# Arduino.net
KiCad netlist of a schematic drawn in EAGLE
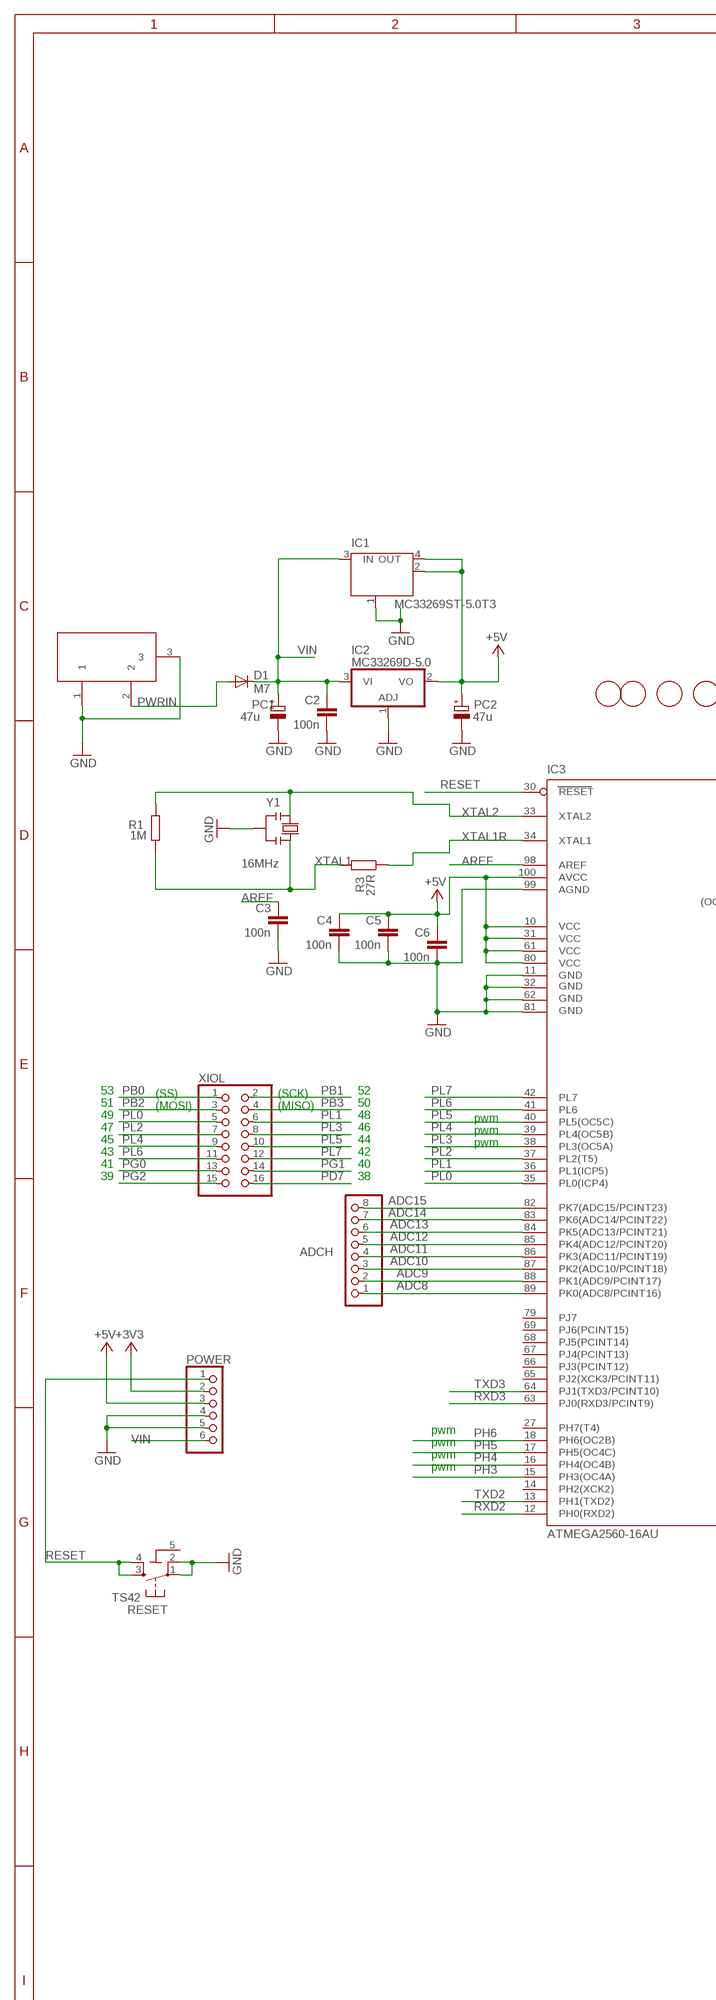
[diagram p0: schematic, sheet 1, part 1 of 2]
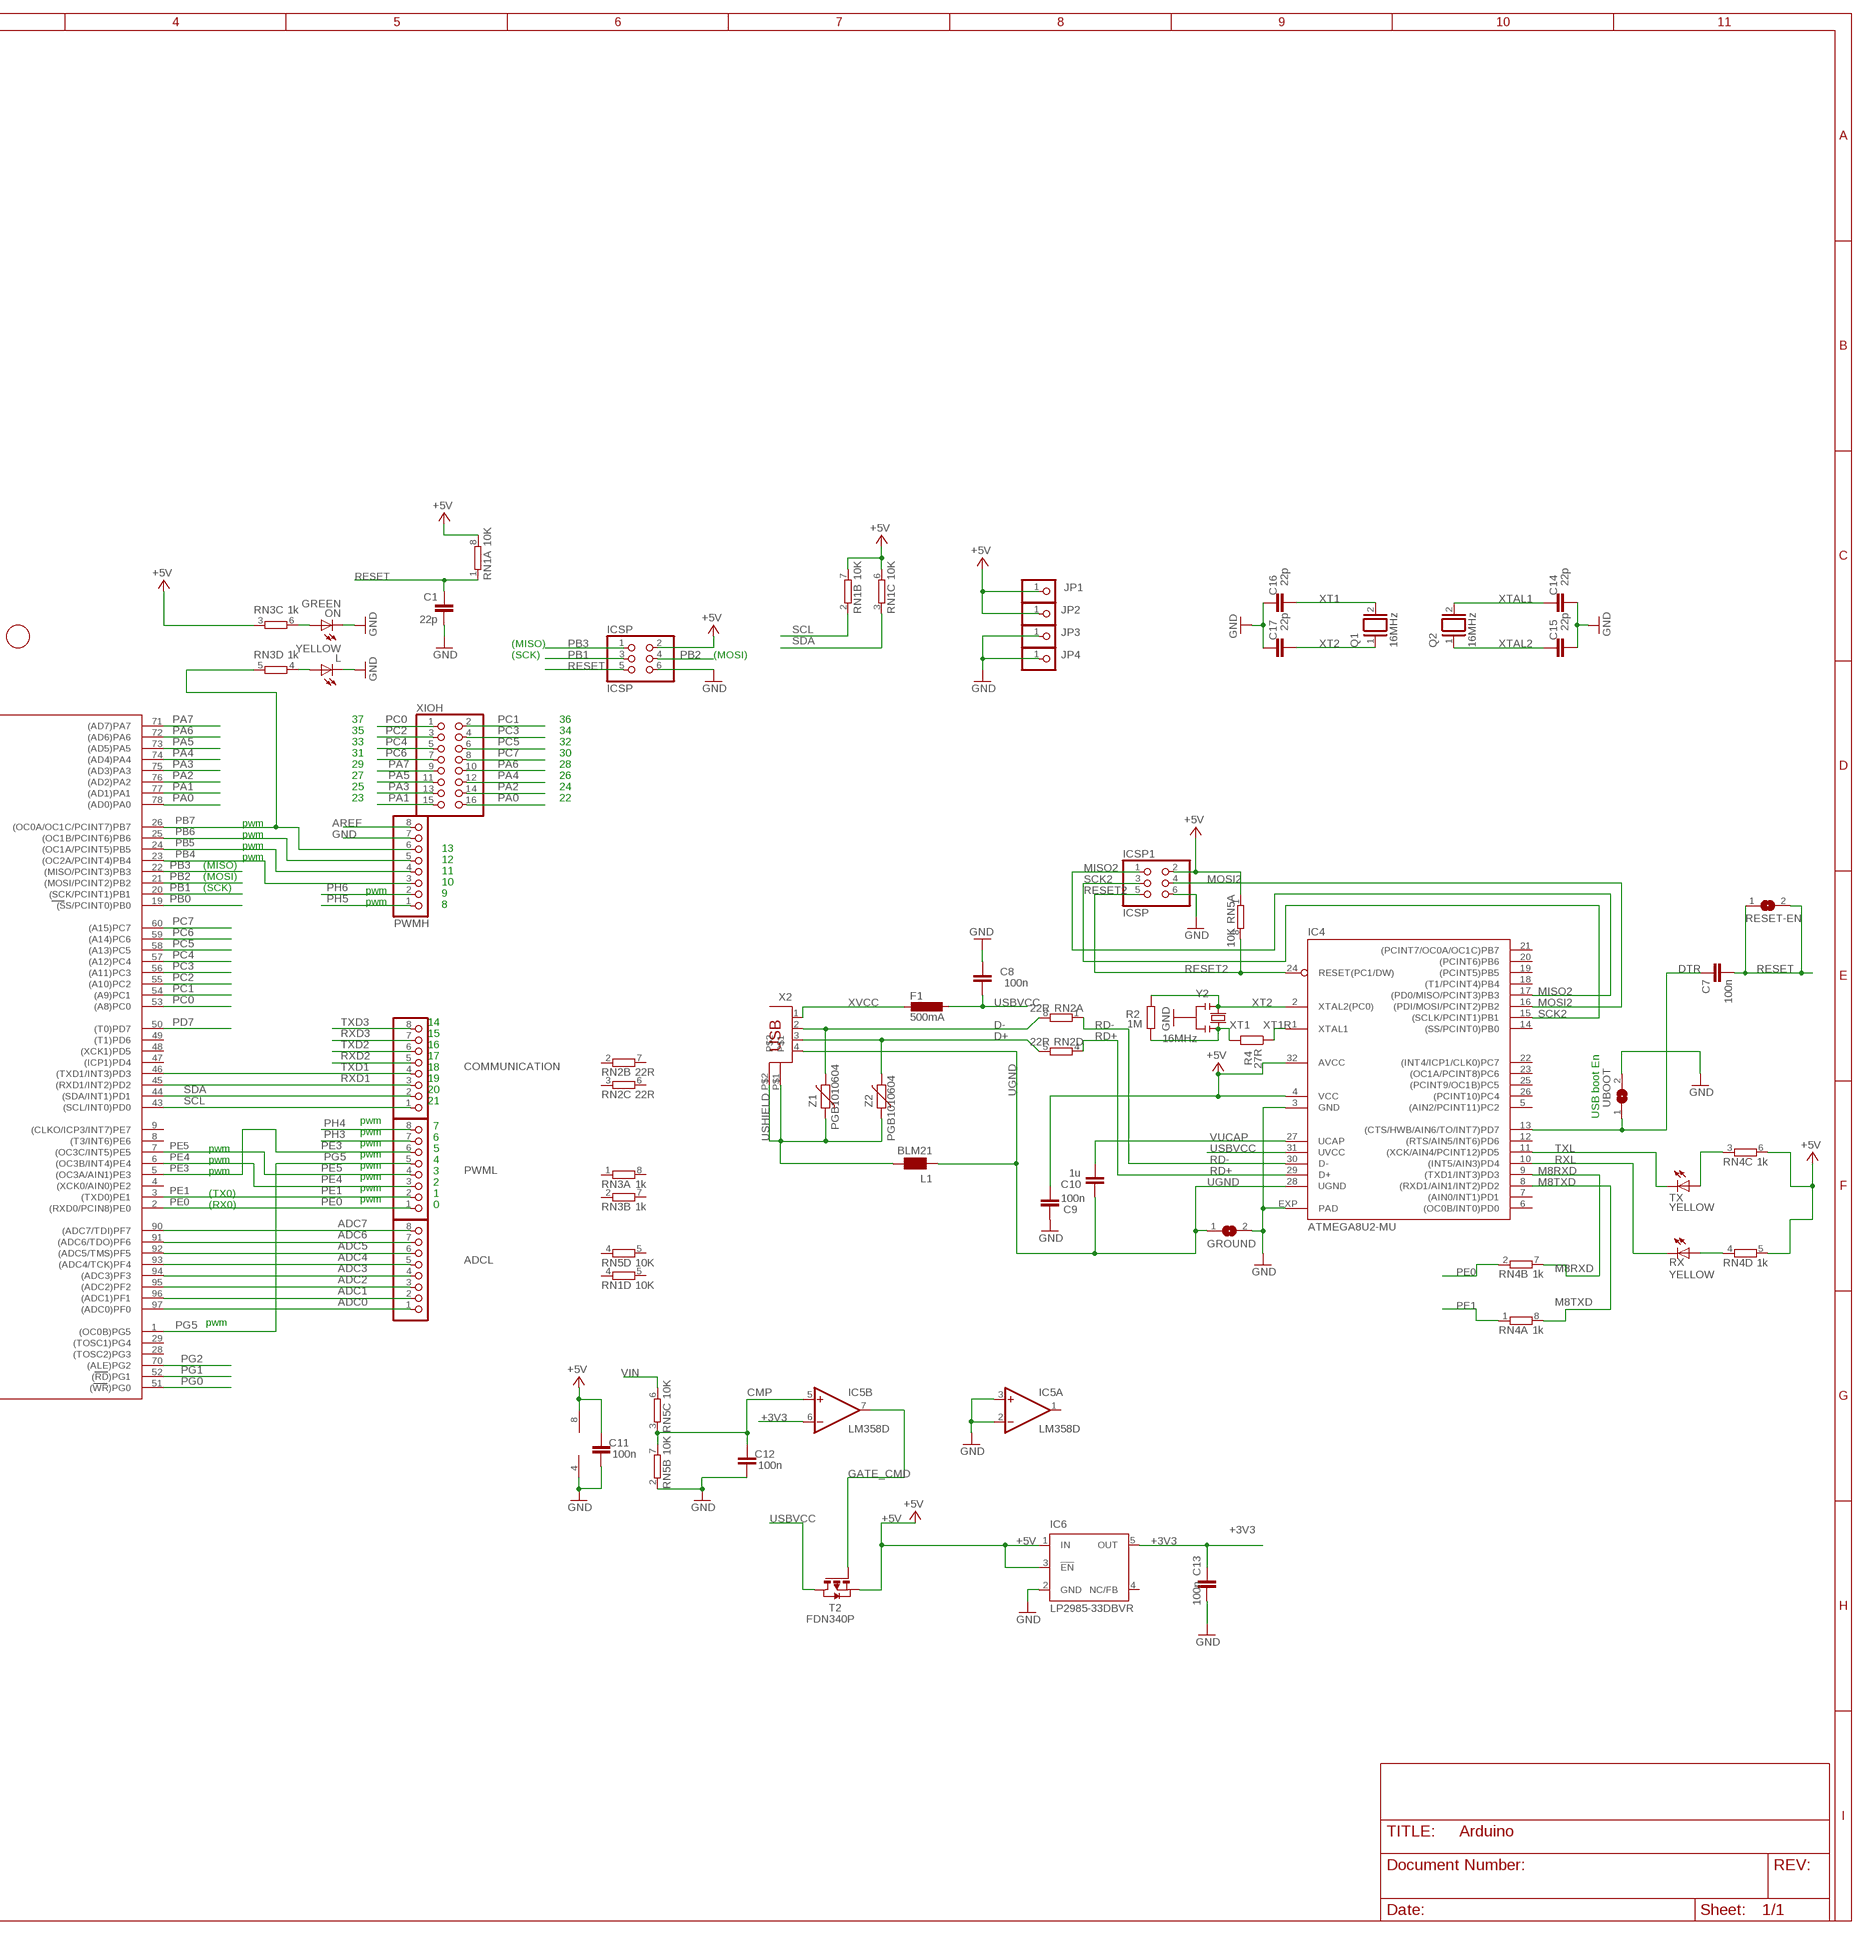
[diagram p1: schematic, sheet 1, part 2 of 2]

(export (version "E")
  (design (tool "Eeschema 10.0.6"))
  (components
    (comp (ref "ADCH")
      (value "PINHD-1X8")
      (footprint "eagle-import:1X08")
      (libsource (lib "eagle-import") (part "PINHD-1X8"))
    )
    (comp (ref "ADCL")
      (value "PINHD-1X8")
      (footprint "eagle-import:1X08")
      (libsource (lib "eagle-import") (part "PINHD-1X8"))
    )
    (comp (ref "C1")
      (value "22p")
      (footprint "eagle-import:C0603-ROUND")
      (libsource (lib "eagle-import") (part "C-EU0603-RND"))
    )
    (comp (ref "C2")
      (value "100n")
      (footprint "eagle-import:C0603-ROUND")
      (libsource (lib "eagle-import") (part "C-EU0603-RND"))
    )
    (comp (ref "C3")
      (value "100n")
      (footprint "eagle-import:C0603-ROUND")
      (libsource (lib "eagle-import") (part "C-EU0603-RND"))
    )
    (comp (ref "C4")
      (value "100n")
      (footprint "eagle-import:C0603-ROUND")
      (libsource (lib "eagle-import") (part "C-EU0603-RND"))
    )
    (comp (ref "C5")
      (value "100n")
      (footprint "eagle-import:C0603-ROUND")
      (libsource (lib "eagle-import") (part "C-EU0603-RND"))
    )
    (comp (ref "C6")
      (value "100n")
      (footprint "eagle-import:C0603-ROUND")
      (libsource (lib "eagle-import") (part "C-EU0603-RND"))
    )
    (comp (ref "C7")
      (value "100n")
      (footprint "eagle-import:C0603-ROUND")
      (libsource (lib "eagle-import") (part "C-EU0603-RND"))
    )
    (comp (ref "C8")
      (value "100n")
      (footprint "eagle-import:C0603")
      (libsource (lib "eagle-import") (part "rcl_C-EUC0603"))
    )
    (comp (ref "C9")
      (value "100n")
      (footprint "eagle-import:C0603-ROUND")
      (libsource (lib "eagle-import") (part "C-EU0603-RND"))
    )
    (comp (ref "C10")
      (value "1u")
      (footprint "eagle-import:C0603-ROUND")
      (libsource (lib "eagle-import") (part "C-EU0603-RND"))
    )
    (comp (ref "C11")
      (value "100n")
      (footprint "eagle-import:C0603")
      (libsource (lib "eagle-import") (part "rcl_C-EUC0603"))
    )
    (comp (ref "C12")
      (value "100n")
      (footprint "eagle-import:C0603-ROUND")
      (libsource (lib "eagle-import") (part "C-EU0603-RND"))
    )
    (comp (ref "C13")
      (value "100n")
      (footprint "eagle-import:C0603-ROUND")
      (libsource (lib "eagle-import") (part "C-EU0603-RND"))
    )
    (comp (ref "C14")
      (value "22p")
      (footprint "eagle-import:C0603-ROUND")
      (libsource (lib "eagle-import") (part "C-EU0603-RND"))
    )
    (comp (ref "C15")
      (value "22p")
      (footprint "eagle-import:C0603-ROUND")
      (libsource (lib "eagle-import") (part "C-EU0603-RND"))
    )
    (comp (ref "C16")
      (value "22p")
      (footprint "eagle-import:C0603-ROUND")
      (libsource (lib "eagle-import") (part "C-EU0603-RND"))
    )
    (comp (ref "C17")
      (value "22p")
      (footprint "eagle-import:C0603-ROUND")
      (libsource (lib "eagle-import") (part "C-EU0603-RND"))
    )
    (comp (ref "COMMUNICATION")
      (value "PINHD-1X8")
      (footprint "eagle-import:1X08")
      (libsource (lib "eagle-import") (part "PINHD-1X8"))
    )
    (comp (ref "D1")
      (value "M7")
      (footprint "eagle-import:SMB")
      (libsource (lib "eagle-import") (part "DIODE-SMB"))
    )
    (comp (ref "F1")
      (value "500mA")
      (footprint "eagle-import:L1812")
      (libsource (lib "eagle-import") (part "L-EUL1812"))
    )
    (comp (ref "GROUND")
      (value "SJ")
      (footprint "eagle-import:SJ")
      (libsource (lib "eagle-import") (part "SJ"))
    )
    (comp (ref "IC1")
      (value "MC33269ST-5.0T3")
      (footprint "eagle-import:SOT223")
      (libsource (lib "eagle-import") (part "MC33269ST-3.3T3"))
    )
    (comp (ref "IC2")
      (value "MC33269D-5.0")
      (footprint "eagle-import:DPACK")
      (libsource (lib "eagle-import") (part "MC33269?D-5.0"))
    )
    (comp (ref "IC3")
      (value "ATMEGA2560-16AU")
      (footprint "eagle-import:TQFP100")
      (libsource (lib "eagle-import") (part "ATMEGAAU1280-16"))
    )
    (comp (ref "IC4")
      (value "ATMEGA8U2-MU")
      (footprint "eagle-import:QFN32")
      (libsource (lib "eagle-import") (part "ATMEGA8U2-MU"))
    )
    (comp (ref "IC5")
      (value "LM358D")
      (footprint "eagle-import:SO08")
      (libsource (lib "eagle-import") (part "LM358D"))
    )
    (comp (ref "IC6")
      (value "LP2985-33DBVR")
      (footprint "eagle-import:SOT23-DBV")
      (libsource (lib "eagle-import") (part "TPS77033"))
    )
    (comp (ref "ICSP")
      (value "ICSP")
      (footprint "eagle-import:2X03")
      (libsource (lib "eagle-import") (part "PINHD-2X3"))
    )
    (comp (ref "ICSP1")
      (value "ICSP")
      (footprint "eagle-import:2X03")
      (libsource (lib "eagle-import") (part "PINHD-2X3"))
    )
    (comp (ref "JP1")
      (value "PINHD-1X1")
      (footprint "eagle-import:1X01")
      (libsource (lib "eagle-import") (part "PINHD-1X1"))
    )
    (comp (ref "JP2")
      (value "PINHD-1X1")
      (footprint "eagle-import:1X01")
      (libsource (lib "eagle-import") (part "PINHD-1X1"))
    )
    (comp (ref "JP3")
      (value "PINHD-1X1")
      (footprint "eagle-import:1X01")
      (libsource (lib "eagle-import") (part "PINHD-1X1"))
    )
    (comp (ref "JP4")
      (value "PINHD-1X1")
      (footprint "eagle-import:1X01")
      (libsource (lib "eagle-import") (part "PINHD-1X1"))
    )
    (comp (ref "L")
      (value "YELLOW")
      (footprint "eagle-import:CHIP-LED0805")
      (libsource (lib "eagle-import") (part "LEDCHIP-LED0805"))
    )
    (comp (ref "L1")
      (value "BLM21")
      (footprint "eagle-import:0805")
      (libsource (lib "eagle-import") (part "WE-CBF_0805"))
    )
    (comp (ref "ON")
      (value "GREEN")
      (footprint "eagle-import:CHIP-LED0805")
      (libsource (lib "eagle-import") (part "LEDCHIP-LED0805"))
    )
    (comp (ref "PC1")
      (value "47u")
      (footprint "eagle-import:PANASONIC_D")
      (libsource (lib "eagle-import") (part "CPOL-EUD"))
    )
    (comp (ref "PC2")
      (value "47u")
      (footprint "eagle-import:PANASONIC_D")
      (libsource (lib "eagle-import") (part "CPOL-EUD"))
    )
    (comp (ref "POWER")
      (value "PINHD-1X6")
      (footprint "eagle-import:1X06")
      (libsource (lib "eagle-import") (part "PINHD-1X6"))
    )
    (comp (ref "PWMH")
      (value "PINHD-1X8")
      (footprint "eagle-import:1X08")
      (libsource (lib "eagle-import") (part "PINHD-1X8"))
    )
    (comp (ref "PWML")
      (value "PINHD-1X8")
      (footprint "eagle-import:1X08")
      (libsource (lib "eagle-import") (part "PINHD-1X8"))
    )
    (comp (ref "Q1")
      (value "16MHz")
      (footprint "eagle-import:QS")
      (libsource (lib "eagle-import") (part "XTAL/S"))
    )
    (comp (ref "Q2")
      (value "16MHz")
      (footprint "eagle-import:QS")
      (libsource (lib "eagle-import") (part "XTAL/S"))
    )
    (comp (ref "R1")
      (value "1M")
      (footprint "eagle-import:R0603-ROUND")
      (libsource (lib "eagle-import") (part "R-EU_R0603"))
    )
    (comp (ref "R2")
      (value "1M")
      (footprint "eagle-import:R0603-ROUND")
      (libsource (lib "eagle-import") (part "R-EU_R0603"))
    )
    (comp (ref "R3")
      (value "27R")
      (footprint "eagle-import:R0603-ROUND")
      (libsource (lib "eagle-import") (part "R-EU_R0603"))
    )
    (comp (ref "R4")
      (value "27R")
      (footprint "eagle-import:R0603-ROUND")
      (libsource (lib "eagle-import") (part "R-EU_R0603"))
    )
    (comp (ref "RESET")
      (value "TS42")
      (footprint "eagle-import:TS42")
      (libsource (lib "eagle-import") (part "TS42"))
    )
    (comp (ref "RESET-EN")
      (value "SJ")
      (footprint "eagle-import:SJ")
      (libsource (lib "eagle-import") (part "SJ"))
    )
    (comp (ref "RN1")
      (value "10K")
      (footprint "eagle-import:CAT16")
      (libsource (lib "eagle-import") (part "4R-NCAT16"))
    )
    (comp (ref "RN2")
      (value "22R")
      (footprint "eagle-import:CAY16")
      (libsource (lib "eagle-import") (part "4R-NCAY16"))
    )
    (comp (ref "RN3")
      (value "1k")
      (footprint "eagle-import:CAY16")
      (libsource (lib "eagle-import") (part "4R-NCAY16"))
    )
    (comp (ref "RN4")
      (value "1k")
      (footprint "eagle-import:CAY16")
      (libsource (lib "eagle-import") (part "4R-NCAY16"))
    )
    (comp (ref "RN5")
      (value "10K")
      (footprint "eagle-import:CAT16")
      (libsource (lib "eagle-import") (part "4R-NCAT16"))
    )
    (comp (ref "RX")
      (value "YELLOW")
      (footprint "eagle-import:CHIP-LED0805")
      (libsource (lib "eagle-import") (part "LEDCHIP-LED0805"))
    )
    (comp (ref "T2")
      (value "FDN340P")
      (footprint "eagle-import:SOT-23")
      (libsource (lib "eagle-import") (part "PMOSSOT23"))
    )
    (comp (ref "TX")
      (value "YELLOW")
      (footprint "eagle-import:CHIP-LED0805")
      (libsource (lib "eagle-import") (part "LEDCHIP-LED0805"))
    )
    (comp (ref "U$2")
      (value "FIDUCIALMOUNT")
      (footprint "eagle-import:FIDUCIA-MOUNT")
      (libsource (lib "eagle-import") (part "FIDUCIALMOUNT"))
    )
    (comp (ref "U$3")
      (value "FIDUCIALMOUNT")
      (footprint "eagle-import:FIDUCIA-MOUNT")
      (libsource (lib "eagle-import") (part "FIDUCIALMOUNT"))
    )
    (comp (ref "U$4")
      (value "FIDUCIALMOUNT")
      (footprint "eagle-import:FIDUCIA-MOUNT")
      (libsource (lib "eagle-import") (part "FIDUCIALMOUNT"))
    )
    (comp (ref "U$5")
      (value "FIDUCIALMOUNT")
      (footprint "eagle-import:FIDUCIA-MOUNT")
      (libsource (lib "eagle-import") (part "FIDUCIALMOUNT"))
    )
    (comp (ref "UBOOT")
      (value "SJ")
      (footprint "eagle-import:SJ")
      (libsource (lib "eagle-import") (part "SJ"))
    )
    (comp (ref "X1")
      (value "DC21MMX")
      (footprint "eagle-import:DC-21MM")
      (libsource (lib "eagle-import") (part "DC21MMX"))
    )
    (comp (ref "X2")
      (value "PN61729")
      (footprint "eagle-import:PN61729")
      (libsource (lib "eagle-import") (part "PN61729"))
    )
    (comp (ref "XIOH")
      (value "PINHD-2X8")
      (footprint "eagle-import:2X08")
      (libsource (lib "eagle-import") (part "PINHD-2X8"))
    )
    (comp (ref "XIOL")
      (value "PINHD-2X8")
      (footprint "eagle-import:2X08")
      (libsource (lib "eagle-import") (part "PINHD-2X8"))
    )
    (comp (ref "Y1")
      (value "16MHz")
      (footprint "eagle-import:RESONATOR")
      (libsource (lib "eagle-import") (part "RESONATORMU"))
    )
    (comp (ref "Y2")
      (value "16MHz")
      (footprint "eagle-import:RESONATOR")
      (libsource (lib "eagle-import") (part "RESONATORMU"))
    )
    (comp (ref "Z1")
      (value "PGB1010604")
      (footprint "eagle-import:CT_CN0603")
      (libsource (lib "eagle-import") (part "VARISTORCN0603"))
    )
    (comp (ref "Z2")
      (value "PGB1010604")
      (footprint "eagle-import:CT_CN0603")
      (libsource (lib "eagle-import") (part "VARISTORCN0603"))
    )
  )
  (nets
    (net (code "1") (name "+3V3") (class "Default")
      (node (ref "C13") (pin "2") (pinfunction "2_2") (pintype "passive"))
      (node (ref "IC5") (pin "6") (pinfunction "-IN_6") (pintype "input"))
      (node (ref "IC6") (pin "5") (pinfunction "OUT_5") (pintype "passive"))
      (node (ref "POWER") (pin "2") (pinfunction "2_2") (pintype "passive"))
    )
    (net (code "2") (name "+5V") (class "Default")
      (node (ref "C11") (pin "2") (pinfunction "2_2") (pintype "passive"))
      (node (ref "C4") (pin "1") (pinfunction "1_1") (pintype "passive"))
      (node (ref "C5") (pin "1") (pinfunction "1_1") (pintype "passive"))
      (node (ref "C6") (pin "1") (pinfunction "1_1") (pintype "passive"))
      (node (ref "C9") (pin "1") (pinfunction "1_1") (pintype "passive"))
      (node (ref "IC1") (pin "2") (pinfunction "OUT_2") (pintype "passive"))
      (node (ref "IC1") (pin "4") (pinfunction "OUT_4") (pintype "passive"))
      (node (ref "IC2") (pin "2") (pinfunction "VO_2") (pintype "passive"))
      (node (ref "IC3") (pin "10") (pinfunction "VCC_10") (pintype "power_in"))
      (node (ref "IC3") (pin "100") (pinfunction "AVCC_100") (pintype "power_in"))
      (node (ref "IC3") (pin "31") (pinfunction "VCC1_31") (pintype "power_in"))
      (node (ref "IC3") (pin "61") (pinfunction "VCC2_61") (pintype "power_in"))
      (node (ref "IC3") (pin "80") (pinfunction "VCC3_80") (pintype "power_in"))
      (node (ref "IC4") (pin "32") (pinfunction "AVCC_32") (pintype "power_in"))
      (node (ref "IC4") (pin "4") (pinfunction "VCC_4") (pintype "power_in"))
      (node (ref "IC5") (pin "8") (pinfunction "V+_8") (pintype "power_in"))
      (node (ref "IC6") (pin "1") (pinfunction "IN_1") (pintype "input"))
      (node (ref "IC6") (pin "3") (pinfunction "~{EN}_3") (pintype "input"))
      (node (ref "ICSP") (pin "2") (pinfunction "2_2") (pintype "passive"))
      (node (ref "ICSP1") (pin "2") (pinfunction "2_2") (pintype "passive"))
      (node (ref "JP1") (pin "1") (pinfunction "1_1") (pintype "passive"))
      (node (ref "JP2") (pin "1") (pinfunction "1_1") (pintype "passive"))
      (node (ref "PC2") (pin "+") (pinfunction "+_+") (pintype "passive"))
      (node (ref "POWER") (pin "3") (pinfunction "3_3") (pintype "passive"))
      (node (ref "RN1") (pin "6") (pinfunction "2_6") (pintype "passive"))
      (node (ref "RN1") (pin "7") (pinfunction "2_7") (pintype "passive"))
      (node (ref "RN1") (pin "8") (pinfunction "2_8") (pintype "passive"))
      (node (ref "RN3") (pin "3") (pinfunction "1_3") (pintype "passive"))
      (node (ref "RN4") (pin "5") (pinfunction "2_5") (pintype "passive"))
      (node (ref "RN4") (pin "6") (pinfunction "2_6") (pintype "passive"))
      (node (ref "RN5") (pin "1") (pinfunction "1_1") (pintype "passive"))
      (node (ref "T2") (pin "2") (pinfunction "S_2") (pintype "passive"))
    )
    (net (code "3") (name "/5-GND") (class "Default")
      (node (ref "RESET") (pin "5") (pinfunction "5-GND_5") (pintype "power_in"))
    )
    (net (code "4") (name "/ADC0") (class "Default")
      (node (ref "ADCL") (pin "1") (pinfunction "1_1") (pintype "passive"))
      (node (ref "IC3") (pin "97") (pinfunction "(ADC0)PF0_97") (pintype "bidirectional"))
    )
    (net (code "5") (name "/ADC1") (class "Default")
      (node (ref "ADCL") (pin "2") (pinfunction "2_2") (pintype "passive"))
      (node (ref "IC3") (pin "96") (pinfunction "(ADC1)PF1_96") (pintype "bidirectional"))
    )
    (net (code "6") (name "/ADC2") (class "Default")
      (node (ref "ADCL") (pin "3") (pinfunction "3_3") (pintype "passive"))
      (node (ref "IC3") (pin "95") (pinfunction "(ADC2)PF2_95") (pintype "bidirectional"))
    )
    (net (code "7") (name "/ADC3") (class "Default")
      (node (ref "ADCL") (pin "4") (pinfunction "4_4") (pintype "passive"))
      (node (ref "IC3") (pin "94") (pinfunction "(ADC3)PF3_94") (pintype "bidirectional"))
    )
    (net (code "8") (name "/ADC4") (class "Default")
      (node (ref "ADCL") (pin "5") (pinfunction "5_5") (pintype "passive"))
      (node (ref "IC3") (pin "93") (pinfunction "(ADC4/TCK)PF4_93") (pintype "bidirectional"))
    )
    (net (code "9") (name "/ADC5") (class "Default")
      (node (ref "ADCL") (pin "6") (pinfunction "6_6") (pintype "passive"))
      (node (ref "IC3") (pin "92") (pinfunction "(ADC5/TMS)PF5_92") (pintype "bidirectional"))
    )
    (net (code "10") (name "/ADC6") (class "Default")
      (node (ref "ADCL") (pin "7") (pinfunction "7_7") (pintype "passive"))
      (node (ref "IC3") (pin "91") (pinfunction "(ADC6/TDO)PF6_91") (pintype "bidirectional"))
    )
    (net (code "11") (name "/ADC7") (class "Default")
      (node (ref "ADCL") (pin "8") (pinfunction "8_8") (pintype "passive"))
      (node (ref "IC3") (pin "90") (pinfunction "(ADC7/TDI)PF7_90") (pintype "bidirectional"))
    )
    (net (code "12") (name "/ADC8") (class "Default")
      (node (ref "ADCH") (pin "1") (pinfunction "1_1") (pintype "passive"))
      (node (ref "IC3") (pin "89") (pinfunction "PK0(ADC8/PCINT16)_89") (pintype "bidirectional"))
    )
    (net (code "13") (name "/ADC9") (class "Default")
      (node (ref "ADCH") (pin "2") (pinfunction "2_2") (pintype "passive"))
      (node (ref "IC3") (pin "88") (pinfunction "PK1(ADC9/PCINT17)_88") (pintype "bidirectional"))
    )
    (net (code "14") (name "/ADC10") (class "Default")
      (node (ref "ADCH") (pin "3") (pinfunction "3_3") (pintype "passive"))
      (node (ref "IC3") (pin "87") (pinfunction "PK2(ADC10/PCINT18)_87") (pintype "bidirectional"))
    )
    (net (code "15") (name "/ADC11") (class "Default")
      (node (ref "ADCH") (pin "4") (pinfunction "4_4") (pintype "passive"))
      (node (ref "IC3") (pin "86") (pinfunction "PK3(ADC11/PCINT19)_86") (pintype "bidirectional"))
    )
    (net (code "16") (name "/ADC12") (class "Default")
      (node (ref "ADCH") (pin "5") (pinfunction "5_5") (pintype "passive"))
      (node (ref "IC3") (pin "85") (pinfunction "PK4(ADC12/PCINT20)_85") (pintype "bidirectional"))
    )
    (net (code "17") (name "/ADC13") (class "Default")
      (node (ref "ADCH") (pin "6") (pinfunction "6_6") (pintype "passive"))
      (node (ref "IC3") (pin "84") (pinfunction "PK5(ADC13/PCINT21)_84") (pintype "bidirectional"))
    )
    (net (code "18") (name "/ADC14") (class "Default")
      (node (ref "ADCH") (pin "7") (pinfunction "7_7") (pintype "passive"))
      (node (ref "IC3") (pin "83") (pinfunction "PK6(ADC14/PCINT22)_83") (pintype "bidirectional"))
    )
    (net (code "19") (name "/ADC15") (class "Default")
      (node (ref "ADCH") (pin "8") (pinfunction "8_8") (pintype "passive"))
      (node (ref "IC3") (pin "82") (pinfunction "PK7(ADC15/PCINT23)_82") (pintype "bidirectional"))
    )
    (net (code "20") (name "/AREF") (class "Default")
      (node (ref "C3") (pin "1") (pinfunction "1_1") (pintype "passive"))
      (node (ref "IC3") (pin "98") (pinfunction "AREF_98") (pintype "bidirectional"))
      (node (ref "PWMH") (pin "8") (pinfunction "8_8") (pintype "passive"))
    )
    (net (code "21") (name "/CMP") (class "Default")
      (node (ref "C12") (pin "2") (pinfunction "2_2") (pintype "passive"))
      (node (ref "IC5") (pin "5") (pinfunction "+IN_5") (pintype "input"))
      (node (ref "RN5") (pin "3") (pinfunction "1_3") (pintype "passive"))
      (node (ref "RN5") (pin "7") (pinfunction "2_7") (pintype "passive"))
    )
    (net (code "22") (name "/D+") (class "Default")
      (node (ref "RN2") (pin "5") (pinfunction "2_5") (pintype "passive"))
      (node (ref "X2") (pin "3") (pinfunction "3_3") (pintype "bidirectional"))
      (node (ref "Z2") (pin "2") (pinfunction "2_2") (pintype "passive"))
    )
    (net (code "23") (name "/D-") (class "Default")
      (node (ref "RN2") (pin "8") (pinfunction "2_8") (pintype "passive"))
      (node (ref "X2") (pin "2") (pinfunction "2_2") (pintype "bidirectional"))
      (node (ref "Z1") (pin "2") (pinfunction "2_2") (pintype "passive"))
    )
    (net (code "24") (name "/DTR") (class "Default")
      (node (ref "C7") (pin "1") (pinfunction "1_1") (pintype "passive"))
      (node (ref "IC4") (pin "13") (pinfunction "(CTS/HWB/AIN6/TO/INT7)PD7_13") (pintype "bidirectional"))
      (node (ref "UBOOT") (pin "1") (pinfunction "1_1") (pintype "passive"))
    )
    (net (code "25") (name "/GATE_CMD") (class "Default")
      (node (ref "IC5") (pin "7") (pinfunction "OUT_7") (pintype "output"))
      (node (ref "T2") (pin "3") (pinfunction "G_3") (pintype "passive"))
    )
    (net (code "26") (name "/M8RXD") (class "Default")
      (node (ref "IC4") (pin "9") (pinfunction "(TXD1/INT3)PD3_9") (pintype "bidirectional"))
      (node (ref "RN4") (pin "7") (pinfunction "2_7") (pintype "passive"))
    )
    (net (code "27") (name "/M8TXD") (class "Default")
      (node (ref "IC4") (pin "8") (pinfunction "(RXD1/AIN1/INT2)PD2_8") (pintype "bidirectional"))
      (node (ref "RN4") (pin "8") (pinfunction "2_8") (pintype "passive"))
    )
    (net (code "28") (name "/MISO2") (class "Default")
      (node (ref "IC4") (pin "17") (pinfunction "(PD0/MISO/PCINT3)PB3_17") (pintype "bidirectional"))
      (node (ref "ICSP1") (pin "1") (pinfunction "1_1") (pintype "passive"))
    )
    (net (code "29") (name "/MOSI2") (class "Default")
      (node (ref "IC4") (pin "16") (pinfunction "(PDI/MOSI/PCINT2)PB2_16") (pintype "bidirectional"))
      (node (ref "ICSP1") (pin "4") (pinfunction "4_4") (pintype "passive"))
    )
    (net (code "30") (name "/PA0") (class "Default")
      (node (ref "IC3") (pin "78") (pinfunction "(AD0)PA0_78") (pintype "bidirectional"))
      (node (ref "XIOH") (pin "16") (pinfunction "16_16") (pintype "passive"))
    )
    (net (code "31") (name "/PA1") (class "Default")
      (node (ref "IC3") (pin "77") (pinfunction "(AD1)PA1_77") (pintype "bidirectional"))
      (node (ref "XIOH") (pin "15") (pinfunction "15_15") (pintype "passive"))
    )
    (net (code "32") (name "/PA2") (class "Default")
      (node (ref "IC3") (pin "76") (pinfunction "(AD2)PA2_76") (pintype "bidirectional"))
      (node (ref "XIOH") (pin "14") (pinfunction "14_14") (pintype "passive"))
    )
    (net (code "33") (name "/PA3") (class "Default")
      (node (ref "IC3") (pin "75") (pinfunction "(AD3)PA3_75") (pintype "bidirectional"))
      (node (ref "XIOH") (pin "13") (pinfunction "13_13") (pintype "passive"))
    )
    (net (code "34") (name "/PA4") (class "Default")
      (node (ref "IC3") (pin "74") (pinfunction "(AD4)PA4_74") (pintype "bidirectional"))
      (node (ref "XIOH") (pin "12") (pinfunction "12_12") (pintype "passive"))
    )
    (net (code "35") (name "/PA5") (class "Default")
      (node (ref "IC3") (pin "73") (pinfunction "(AD5)PA5_73") (pintype "bidirectional"))
      (node (ref "XIOH") (pin "11") (pinfunction "11_11") (pintype "passive"))
    )
    (net (code "36") (name "/PA6") (class "Default")
      (node (ref "IC3") (pin "72") (pinfunction "(AD6)PA6_72") (pintype "bidirectional"))
      (node (ref "XIOH") (pin "10") (pinfunction "10_10") (pintype "passive"))
    )
    (net (code "37") (name "/PA7") (class "Default")
      (node (ref "IC3") (pin "71") (pinfunction "(AD7)PA7_71") (pintype "bidirectional"))
      (node (ref "XIOH") (pin "9") (pinfunction "9_9") (pintype "passive"))
    )
    (net (code "38") (name "/PB0") (class "Default")
      (node (ref "IC3") (pin "19") (pinfunction "(SS/PCINT0)PB0_19") (pintype "bidirectional"))
      (node (ref "XIOL") (pin "1") (pinfunction "1_1") (pintype "passive"))
    )
    (net (code "39") (name "/PB1") (class "Default")
      (node (ref "IC3") (pin "20") (pinfunction "(SCK/PCINT1)PB1_20") (pintype "bidirectional"))
      (node (ref "ICSP") (pin "3") (pinfunction "3_3") (pintype "passive"))
      (node (ref "XIOL") (pin "2") (pinfunction "2_2") (pintype "passive"))
    )
    (net (code "40") (name "/PB2") (class "Default")
      (node (ref "IC3") (pin "21") (pinfunction "(MOSI/PCINT2)PB2_21") (pintype "bidirectional"))
      (node (ref "ICSP") (pin "4") (pinfunction "4_4") (pintype "passive"))
      (node (ref "XIOL") (pin "3") (pinfunction "3_3") (pintype "passive"))
    )
    (net (code "41") (name "/PB3") (class "Default")
      (node (ref "IC3") (pin "22") (pinfunction "(MISO/PCINT3)PB3_22") (pintype "bidirectional"))
      (node (ref "ICSP") (pin "1") (pinfunction "1_1") (pintype "passive"))
      (node (ref "XIOL") (pin "4") (pinfunction "4_4") (pintype "passive"))
    )
    (net (code "42") (name "/PB4") (class "Default")
      (node (ref "IC3") (pin "23") (pinfunction "(OC2A/PCINT4)PB4_23") (pintype "bidirectional"))
      (node (ref "PWMH") (pin "3") (pinfunction "3_3") (pintype "passive"))
    )
    (net (code "43") (name "/PB5") (class "Default")
      (node (ref "IC3") (pin "24") (pinfunction "(OC1A/PCINT5)PB5_24") (pintype "bidirectional"))
      (node (ref "PWMH") (pin "4") (pinfunction "4_4") (pintype "passive"))
    )
    (net (code "44") (name "/PB6") (class "Default")
      (node (ref "IC3") (pin "25") (pinfunction "(OC1B/PCINT6)PB6_25") (pintype "bidirectional"))
      (node (ref "PWMH") (pin "5") (pinfunction "5_5") (pintype "passive"))
    )
    (net (code "45") (name "/PB7") (class "Default")
      (node (ref "IC3") (pin "26") (pinfunction "(OC0A/OC1C/PCINT7)PB7_26") (pintype "bidirectional"))
      (node (ref "PWMH") (pin "6") (pinfunction "6_6") (pintype "passive"))
      (node (ref "RN3") (pin "5") (pinfunction "2_5") (pintype "passive"))
    )
    (net (code "46") (name "/PC0") (class "Default")
      (node (ref "IC3") (pin "53") (pinfunction "(A8)PC0_53") (pintype "bidirectional"))
      (node (ref "XIOH") (pin "1") (pinfunction "1_1") (pintype "passive"))
    )
    (net (code "47") (name "/PC1") (class "Default")
      (node (ref "IC3") (pin "54") (pinfunction "(A9)PC1_54") (pintype "bidirectional"))
      (node (ref "XIOH") (pin "2") (pinfunction "2_2") (pintype "passive"))
    )
    (net (code "48") (name "/PC2") (class "Default")
      (node (ref "IC3") (pin "55") (pinfunction "(A10)PC2_55") (pintype "bidirectional"))
      (node (ref "XIOH") (pin "3") (pinfunction "3_3") (pintype "passive"))
    )
    (net (code "49") (name "/PC3") (class "Default")
      (node (ref "IC3") (pin "56") (pinfunction "(A11)PC3_56") (pintype "bidirectional"))
      (node (ref "XIOH") (pin "4") (pinfunction "4_4") (pintype "passive"))
    )
    (net (code "50") (name "/PC4") (class "Default")
      (node (ref "IC3") (pin "57") (pinfunction "(A12)PC4_57") (pintype "bidirectional"))
      (node (ref "XIOH") (pin "5") (pinfunction "5_5") (pintype "passive"))
    )
    (net (code "51") (name "/PC5") (class "Default")
      (node (ref "IC3") (pin "58") (pinfunction "(A13)PC5_58") (pintype "bidirectional"))
      (node (ref "XIOH") (pin "6") (pinfunction "6_6") (pintype "passive"))
    )
    (net (code "52") (name "/PC6") (class "Default")
      (node (ref "IC3") (pin "59") (pinfunction "(A14)PC6_59") (pintype "bidirectional"))
      (node (ref "XIOH") (pin "7") (pinfunction "7_7") (pintype "passive"))
    )
    (net (code "53") (name "/PC7") (class "Default")
      (node (ref "IC3") (pin "60") (pinfunction "(A15)PC7_60") (pintype "bidirectional"))
      (node (ref "XIOH") (pin "8") (pinfunction "8_8") (pintype "passive"))
    )
    (net (code "54") (name "/PD7") (class "Default")
      (node (ref "IC3") (pin "50") (pinfunction "(T0)PD7_50") (pintype "bidirectional"))
      (node (ref "XIOL") (pin "16") (pinfunction "16_16") (pintype "passive"))
    )
    (net (code "55") (name "/PE0") (class "Default")
      (node (ref "IC3") (pin "2") (pinfunction "(RXD0/PCIN8)PE0_2") (pintype "bidirectional"))
      (node (ref "PWML") (pin "1") (pinfunction "1_1") (pintype "passive"))
      (node (ref "RN4") (pin "2") (pinfunction "1_2") (pintype "passive"))
    )
    (net (code "56") (name "/PE1") (class "Default")
      (node (ref "IC3") (pin "3") (pinfunction "(TXD0)PE1_3") (pintype "bidirectional"))
      (node (ref "PWML") (pin "2") (pinfunction "2_2") (pintype "passive"))
      (node (ref "RN4") (pin "1") (pinfunction "1_1") (pintype "passive"))
    )
    (net (code "57") (name "/PE3") (class "Default")
      (node (ref "IC3") (pin "5") (pinfunction "(OC3A/AIN1)PE3_5") (pintype "bidirectional"))
      (node (ref "PWML") (pin "6") (pinfunction "6_6") (pintype "passive"))
    )
    (net (code "58") (name "/PE4") (class "Default")
      (node (ref "IC3") (pin "6") (pinfunction "(OC3B/INT4)PE4_6") (pintype "bidirectional"))
      (node (ref "PWML") (pin "3") (pinfunction "3_3") (pintype "passive"))
    )
    (net (code "59") (name "/PE5") (class "Default")
      (node (ref "IC3") (pin "7") (pinfunction "(OC3C/INT5)PE5_7") (pintype "bidirectional"))
      (node (ref "PWML") (pin "4") (pinfunction "4_4") (pintype "passive"))
    )
    (net (code "60") (name "/PG0") (class "Default")
      (node (ref "IC3") (pin "51") (pinfunction "(WR)PG0_51") (pintype "bidirectional"))
      (node (ref "XIOL") (pin "13") (pinfunction "13_13") (pintype "passive"))
    )
    (net (code "61") (name "/PG1") (class "Default")
      (node (ref "IC3") (pin "52") (pinfunction "(RD)PG1_52") (pintype "bidirectional"))
      (node (ref "XIOL") (pin "14") (pinfunction "14_14") (pintype "passive"))
    )
    (net (code "62") (name "/PG2") (class "Default")
      (node (ref "IC3") (pin "70") (pinfunction "(ALE)PG2_70") (pintype "bidirectional"))
      (node (ref "XIOL") (pin "15") (pinfunction "15_15") (pintype "passive"))
    )
    (net (code "63") (name "/PG5") (class "Default")
      (node (ref "IC3") (pin "1") (pinfunction "(OC0B)PG5_1") (pintype "bidirectional"))
      (node (ref "PWML") (pin "5") (pinfunction "5_5") (pintype "passive"))
    )
    (net (code "64") (name "/PH3") (class "Default")
      (node (ref "IC3") (pin "15") (pinfunction "PH3(OC4A)_15") (pintype "bidirectional"))
      (node (ref "PWML") (pin "7") (pinfunction "7_7") (pintype "passive"))
    )
    (net (code "65") (name "/PH4") (class "Default")
      (node (ref "IC3") (pin "16") (pinfunction "PH4(OC4B)_16") (pintype "bidirectional"))
      (node (ref "PWML") (pin "8") (pinfunction "8_8") (pintype "passive"))
    )
    (net (code "66") (name "/PH5") (class "Default")
      (node (ref "IC3") (pin "17") (pinfunction "PH5(OC4C)_17") (pintype "bidirectional"))
      (node (ref "PWMH") (pin "1") (pinfunction "1_1") (pintype "passive"))
    )
    (net (code "67") (name "/PH6") (class "Default")
      (node (ref "IC3") (pin "18") (pinfunction "PH6(OC2B)_18") (pintype "bidirectional"))
      (node (ref "PWMH") (pin "2") (pinfunction "2_2") (pintype "passive"))
    )
    (net (code "68") (name "/PL0") (class "Default")
      (node (ref "IC3") (pin "35") (pinfunction "PL0(ICP4)_35") (pintype "bidirectional"))
      (node (ref "XIOL") (pin "5") (pinfunction "5_5") (pintype "passive"))
    )
    (net (code "69") (name "/PL1") (class "Default")
      (node (ref "IC3") (pin "36") (pinfunction "PL1(ICP5)_36") (pintype "bidirectional"))
      (node (ref "XIOL") (pin "6") (pinfunction "6_6") (pintype "passive"))
    )
    (net (code "70") (name "/PL2") (class "Default")
      (node (ref "IC3") (pin "37") (pinfunction "PL2(T5)_37") (pintype "bidirectional"))
      (node (ref "XIOL") (pin "7") (pinfunction "7_7") (pintype "passive"))
    )
    (net (code "71") (name "/PL3") (class "Default")
      (node (ref "IC3") (pin "38") (pinfunction "PL3(OC5A)_38") (pintype "bidirectional"))
      (node (ref "XIOL") (pin "8") (pinfunction "8_8") (pintype "passive"))
    )
    (net (code "72") (name "/PL4") (class "Default")
      (node (ref "IC3") (pin "39") (pinfunction "PL4(OC5B)_39") (pintype "bidirectional"))
      (node (ref "XIOL") (pin "9") (pinfunction "9_9") (pintype "passive"))
    )
    (net (code "73") (name "/PL5") (class "Default")
      (node (ref "IC3") (pin "40") (pinfunction "PL5(OC5C)_40") (pintype "bidirectional"))
      (node (ref "XIOL") (pin "10") (pinfunction "10_10") (pintype "passive"))
    )
    (net (code "74") (name "/PL6") (class "Default")
      (node (ref "IC3") (pin "41") (pinfunction "PL6_41") (pintype "bidirectional"))
      (node (ref "XIOL") (pin "11") (pinfunction "11_11") (pintype "passive"))
    )
    (net (code "75") (name "/PL7") (class "Default")
      (node (ref "IC3") (pin "42") (pinfunction "PL7_42") (pintype "bidirectional"))
      (node (ref "XIOL") (pin "12") (pinfunction "12_12") (pintype "passive"))
    )
    (net (code "76") (name "/PWRIN") (class "Default")
      (node (ref "D1") (pin "A") (pinfunction "A_A") (pintype "passive"))
      (node (ref "X1") (pin "2") (pinfunction "2_2") (pintype "power_in"))
    )
    (net (code "77") (name "/RD+") (class "Default")
      (node (ref "IC4") (pin "29") (pinfunction "D+_29") (pintype "bidirectional"))
      (node (ref "RN2") (pin "4") (pinfunction "1_4") (pintype "passive"))
    )
    (net (code "78") (name "/RD-") (class "Default")
      (node (ref "IC4") (pin "30") (pinfunction "D-_30") (pintype "bidirectional"))
      (node (ref "RN2") (pin "1") (pinfunction "1_1") (pintype "passive"))
    )
    (net (code "79") (name "/RESET") (class "Default")
      (node (ref "C1") (pin "1") (pinfunction "1_1") (pintype "passive"))
      (node (ref "C7") (pin "2") (pinfunction "2_2") (pintype "passive"))
      (node (ref "IC3") (pin "30") (pinfunction "RESET_30") (pintype "input"))
      (node (ref "ICSP") (pin "5") (pinfunction "5_5") (pintype "passive"))
      (node (ref "POWER") (pin "1") (pinfunction "1_1") (pintype "passive"))
      (node (ref "RESET") (pin "3") (pinfunction "3_3") (pintype "passive"))
      (node (ref "RESET") (pin "4") (pinfunction "4_4") (pintype "passive"))
      (node (ref "RESET-EN") (pin "1") (pinfunction "1_1") (pintype "passive"))
      (node (ref "RESET-EN") (pin "2") (pinfunction "2_2") (pintype "passive"))
      (node (ref "RN1") (pin "1") (pinfunction "1_1") (pintype "passive"))
    )
    (net (code "80") (name "/RESET2") (class "Default")
      (node (ref "IC4") (pin "24") (pinfunction "RESET(PC1/DW)_24") (pintype "input"))
      (node (ref "ICSP1") (pin "5") (pinfunction "5_5") (pintype "passive"))
      (node (ref "RN5") (pin "8") (pinfunction "2_8") (pintype "passive"))
    )
    (net (code "81") (name "/RXD1") (class "Default")
      (node (ref "COMMUNICATION") (pin "3") (pinfunction "3_3") (pintype "passive"))
      (node (ref "IC3") (pin "45") (pinfunction "(RXD1/INT2)PD2_45") (pintype "bidirectional"))
    )
    (net (code "82") (name "/RXD2") (class "Default")
      (node (ref "COMMUNICATION") (pin "5") (pinfunction "5_5") (pintype "passive"))
      (node (ref "IC3") (pin "12") (pinfunction "PH0(RXD2)_12") (pintype "bidirectional"))
    )
    (net (code "83") (name "/RXD3") (class "Default")
      (node (ref "COMMUNICATION") (pin "7") (pinfunction "7_7") (pintype "passive"))
      (node (ref "IC3") (pin "63") (pinfunction "PJ0(RXD3/PCINT9)_63") (pintype "bidirectional"))
    )
    (net (code "84") (name "/RXL") (class "Default")
      (node (ref "IC4") (pin "10") (pinfunction "(INT5/AIN3)PD4_10") (pintype "bidirectional"))
      (node (ref "RX") (pin "C") (pinfunction "C_C") (pintype "passive"))
    )
    (net (code "85") (name "/SCK2") (class "Default")
      (node (ref "IC4") (pin "15") (pinfunction "(SCLK/PCINT1)PB1_15") (pintype "bidirectional"))
      (node (ref "ICSP1") (pin "3") (pinfunction "3_3") (pintype "passive"))
    )
    (net (code "86") (name "/SCL") (class "Default")
      (node (ref "COMMUNICATION") (pin "1") (pinfunction "1_1") (pintype "passive"))
      (node (ref "IC3") (pin "43") (pinfunction "(SCL/INT0)PD0_43") (pintype "bidirectional"))
      (node (ref "RN1") (pin "2") (pinfunction "1_2") (pintype "passive"))
    )
    (net (code "87") (name "/SDA") (class "Default")
      (node (ref "COMMUNICATION") (pin "2") (pinfunction "2_2") (pintype "passive"))
      (node (ref "IC3") (pin "44") (pinfunction "(SDA/INT1)PD1_44") (pintype "bidirectional"))
      (node (ref "RN1") (pin "3") (pinfunction "1_3") (pintype "passive"))
    )
    (net (code "88") (name "/TXD1") (class "Default")
      (node (ref "COMMUNICATION") (pin "4") (pinfunction "4_4") (pintype "passive"))
      (node (ref "IC3") (pin "46") (pinfunction "(TXD1/INT3)PD3_46") (pintype "bidirectional"))
    )
    (net (code "89") (name "/TXD2") (class "Default")
      (node (ref "COMMUNICATION") (pin "6") (pinfunction "6_6") (pintype "passive"))
      (node (ref "IC3") (pin "13") (pinfunction "PH1(TXD2)_13") (pintype "bidirectional"))
    )
    (net (code "90") (name "/TXD3") (class "Default")
      (node (ref "COMMUNICATION") (pin "8") (pinfunction "8_8") (pintype "passive"))
      (node (ref "IC3") (pin "64") (pinfunction "PJ1(TXD3/PCINT10)_64") (pintype "bidirectional"))
    )
    (net (code "91") (name "/TXL") (class "Default")
      (node (ref "IC4") (pin "11") (pinfunction "(XCK/AIN4/PCINT12)PD5_11") (pintype "bidirectional"))
      (node (ref "TX") (pin "C") (pinfunction "C_C") (pintype "passive"))
    )
    (net (code "92") (name "/UGND") (class "Default")
      (node (ref "C10") (pin "2") (pinfunction "2_2") (pintype "passive"))
      (node (ref "GROUND") (pin "1") (pinfunction "1_1") (pintype "passive"))
      (node (ref "IC4") (pin "28") (pinfunction "UGND_28") (pintype "power_in"))
      (node (ref "L1") (pin "1") (pinfunction "1_1") (pintype "passive"))
      (node (ref "X2") (pin "4") (pinfunction "4_4") (pintype "bidirectional"))
    )
    (net (code "93") (name "/USBVCC") (class "Default")
      (node (ref "C8") (pin "1") (pinfunction "1_1") (pintype "passive"))
      (node (ref "F1") (pin "1") (pinfunction "1_1") (pintype "passive"))
      (node (ref "IC4") (pin "31") (pinfunction "UVCC_31") (pintype "power_in"))
      (node (ref "T2") (pin "1") (pinfunction "D_1") (pintype "passive"))
    )
    (net (code "94") (name "/USHIELD") (class "Default")
      (node (ref "L1") (pin "2") (pinfunction "2_2") (pintype "passive"))
      (node (ref "X2") (pin "P$1") (pinfunction "P$1_P$1") (pintype "bidirectional"))
      (node (ref "X2") (pin "P$2") (pinfunction "P$2_P$2") (pintype "bidirectional"))
      (node (ref "Z1") (pin "1") (pinfunction "1_1") (pintype "passive"))
      (node (ref "Z2") (pin "1") (pinfunction "1_1") (pintype "passive"))
    )
    (net (code "95") (name "/VIN") (class "Default")
      (node (ref "C2") (pin "1") (pinfunction "1_1") (pintype "passive"))
      (node (ref "D1") (pin "C") (pinfunction "C_C") (pintype "passive"))
      (node (ref "IC1") (pin "3") (pinfunction "IN_3") (pintype "input"))
      (node (ref "IC2") (pin "3") (pinfunction "VI_3") (pintype "input"))
      (node (ref "PC1") (pin "+") (pinfunction "+_+") (pintype "passive"))
      (node (ref "POWER") (pin "6") (pinfunction "6_6") (pintype "passive"))
      (node (ref "RN5") (pin "6") (pinfunction "2_6") (pintype "passive"))
    )
    (net (code "96") (name "/VUCAP") (class "Default")
      (node (ref "C10") (pin "1") (pinfunction "1_1") (pintype "passive"))
      (node (ref "IC4") (pin "27") (pinfunction "UCAP_27") (pintype "passive"))
    )
    (net (code "97") (name "/XT1") (class "Default")
      (node (ref "C16") (pin "1") (pinfunction "1_1") (pintype "passive"))
      (node (ref "Q1") (pin "2") (pinfunction "2_2") (pintype "passive"))
      (node (ref "R2") (pin "1") (pinfunction "1_1") (pintype "passive"))
      (node (ref "R4") (pin "2") (pinfunction "2_2") (pintype "passive"))
      (node (ref "Y2") (pin "3") (pinfunction "3_3") (pintype "passive"))
    )
    (net (code "98") (name "/XT1R") (class "Default")
      (node (ref "IC4") (pin "1") (pinfunction "XTAL1_1") (pintype "bidirectional"))
      (node (ref "R4") (pin "1") (pinfunction "1_1") (pintype "passive"))
    )
    (net (code "99") (name "/XT2") (class "Default")
      (node (ref "C17") (pin "1") (pinfunction "1_1") (pintype "passive"))
      (node (ref "IC4") (pin "2") (pinfunction "XTAL2(PC0)_2") (pintype "bidirectional"))
      (node (ref "Q1") (pin "1") (pinfunction "1_1") (pintype "passive"))
      (node (ref "R2") (pin "2") (pinfunction "2_2") (pintype "passive"))
      (node (ref "Y2") (pin "1") (pinfunction "1_1") (pintype "passive"))
    )
    (net (code "100") (name "/XTAL1") (class "Default")
      (node (ref "C14") (pin "2") (pinfunction "2_2") (pintype "passive"))
      (node (ref "Q2") (pin "2") (pinfunction "2_2") (pintype "passive"))
      (node (ref "R1") (pin "1") (pinfunction "1_1") (pintype "passive"))
      (node (ref "R3") (pin "2") (pinfunction "2_2") (pintype "passive"))
      (node (ref "Y1") (pin "3") (pinfunction "3_3") (pintype "passive"))
    )
    (net (code "101") (name "/XTAL1R") (class "Default")
      (node (ref "IC3") (pin "34") (pinfunction "XTAL1_34") (pintype "input"))
      (node (ref "R3") (pin "1") (pinfunction "1_1") (pintype "passive"))
    )
    (net (code "102") (name "/XTAL2") (class "Default")
      (node (ref "C15") (pin "2") (pinfunction "2_2") (pintype "passive"))
      (node (ref "IC3") (pin "33") (pinfunction "XTAL2_33") (pintype "output"))
      (node (ref "Q2") (pin "1") (pinfunction "1_1") (pintype "passive"))
      (node (ref "R1") (pin "2") (pinfunction "2_2") (pintype "passive"))
      (node (ref "Y1") (pin "1") (pinfunction "1_1") (pintype "passive"))
    )
    (net (code "103") (name "/XVCC") (class "Default")
      (node (ref "F1") (pin "2") (pinfunction "2_2") (pintype "passive"))
      (node (ref "X2") (pin "1") (pinfunction "1_1") (pintype "bidirectional"))
    )
    (net (code "104") (name "GND") (class "Default")
      (node (ref "C1") (pin "2") (pinfunction "2_2") (pintype "passive"))
      (node (ref "C11") (pin "1") (pinfunction "1_1") (pintype "passive"))
      (node (ref "C12") (pin "1") (pinfunction "1_1") (pintype "passive"))
      (node (ref "C13") (pin "1") (pinfunction "1_1") (pintype "passive"))
      (node (ref "C14") (pin "1") (pinfunction "1_1") (pintype "passive"))
      (node (ref "C15") (pin "1") (pinfunction "1_1") (pintype "passive"))
      (node (ref "C16") (pin "2") (pinfunction "2_2") (pintype "passive"))
      (node (ref "C17") (pin "2") (pinfunction "2_2") (pintype "passive"))
      (node (ref "C2") (pin "2") (pinfunction "2_2") (pintype "passive"))
      (node (ref "C3") (pin "2") (pinfunction "2_2") (pintype "passive"))
      (node (ref "C4") (pin "2") (pinfunction "2_2") (pintype "passive"))
      (node (ref "C5") (pin "2") (pinfunction "2_2") (pintype "passive"))
      (node (ref "C6") (pin "2") (pinfunction "2_2") (pintype "passive"))
      (node (ref "C8") (pin "2") (pinfunction "2_2") (pintype "passive"))
      (node (ref "C9") (pin "2") (pinfunction "2_2") (pintype "passive"))
      (node (ref "GROUND") (pin "2") (pinfunction "2_2") (pintype "passive"))
      (node (ref "IC1") (pin "1") (pinfunction "GND/ADJ_1") (pintype "input"))
      (node (ref "IC2") (pin "1") (pinfunction "ADJ_1") (pintype "input"))
      (node (ref "IC3") (pin "11") (pinfunction "GND_11") (pintype "power_in"))
      (node (ref "IC3") (pin "32") (pinfunction "GND1_32") (pintype "power_in"))
      (node (ref "IC3") (pin "62") (pinfunction "GND2_62") (pintype "power_in"))
      (node (ref "IC3") (pin "81") (pinfunction "GND3_81") (pintype "power_in"))
      (node (ref "IC3") (pin "99") (pinfunction "AGND_99") (pintype "power_in"))
      (node (ref "IC4") (pin "3") (pinfunction "GND_3") (pintype "power_in"))
      (node (ref "IC4") (pin "EXP") (pinfunction "PAD_EXP") (pintype "power_in"))
      (node (ref "IC5") (pin "2") (pinfunction "-IN_2") (pintype "input"))
      (node (ref "IC5") (pin "3") (pinfunction "+IN_3") (pintype "input"))
      (node (ref "IC5") (pin "4") (pinfunction "V-_4") (pintype "power_in"))
      (node (ref "IC6") (pin "2") (pinfunction "GND_2") (pintype "power_in"))
      (node (ref "ICSP") (pin "6") (pinfunction "6_6") (pintype "passive"))
      (node (ref "ICSP1") (pin "6") (pinfunction "6_6") (pintype "passive"))
      (node (ref "JP3") (pin "1") (pinfunction "1_1") (pintype "passive"))
      (node (ref "JP4") (pin "1") (pinfunction "1_1") (pintype "passive"))
      (node (ref "L") (pin "C") (pinfunction "C_C") (pintype "passive"))
      (node (ref "ON") (pin "C") (pinfunction "C_C") (pintype "passive"))
      (node (ref "PC1") (pin "-") (pinfunction "-_-") (pintype "passive"))
      (node (ref "PC2") (pin "-") (pinfunction "-_-") (pintype "passive"))
      (node (ref "POWER") (pin "4") (pinfunction "4_4") (pintype "passive"))
      (node (ref "POWER") (pin "5") (pinfunction "5_5") (pintype "passive"))
      (node (ref "PWMH") (pin "7") (pinfunction "7_7") (pintype "passive"))
      (node (ref "RESET") (pin "1") (pinfunction "1_1") (pintype "passive"))
      (node (ref "RESET") (pin "2") (pinfunction "2_2") (pintype "passive"))
      (node (ref "RN5") (pin "2") (pinfunction "1_2") (pintype "passive"))
      (node (ref "UBOOT") (pin "2") (pinfunction "2_2") (pintype "passive"))
      (node (ref "X1") (pin "1") (pinfunction "1_1") (pintype "power_in"))
      (node (ref "X1") (pin "3") (pinfunction "3_3") (pintype "power_in"))
      (node (ref "Y1") (pin "2") (pinfunction "2_2") (pintype "passive"))
      (node (ref "Y2") (pin "2") (pinfunction "2_2") (pintype "passive"))
    )
    (net (code "105") (name "Net-(RN3C-2)") (class "Default")
      (node (ref "ON") (pin "A") (pinfunction "A_A") (pintype "passive"))
      (node (ref "RN3") (pin "6") (pinfunction "2_6") (pintype "passive"))
    )
    (net (code "106") (name "Net-(RN3D-1)") (class "Default")
      (node (ref "L") (pin "A") (pinfunction "A_A") (pintype "passive"))
      (node (ref "RN3") (pin "4") (pinfunction "1_4") (pintype "passive"))
    )
    (net (code "107") (name "Net-(RN4C-1)") (class "Default")
      (node (ref "RN4") (pin "3") (pinfunction "1_3") (pintype "passive"))
      (node (ref "TX") (pin "A") (pinfunction "A_A") (pintype "passive"))
    )
    (net (code "108") (name "Net-(RN4D-1)") (class "Default")
      (node (ref "RN4") (pin "4") (pinfunction "1_4") (pintype "passive"))
      (node (ref "RX") (pin "A") (pinfunction "A_A") (pintype "passive"))
    )
    (net (code "109") (name "unconnected-(IC3-(CLKO{slash}ICP3{slash}INT7)PE7-Pad9)") (class "Default")
      (node (ref "IC3") (pin "9") (pinfunction "(CLKO/ICP3/INT7)PE7_9") (pintype "bidirectional"))
    )
    (net (code "110") (name "unconnected-(IC3-(ICP1)PD4-Pad47)") (class "Default")
      (node (ref "IC3") (pin "47") (pinfunction "(ICP1)PD4_47") (pintype "bidirectional"))
    )
    (net (code "111") (name "unconnected-(IC3-(T1)PD6-Pad49)") (class "Default")
      (node (ref "IC3") (pin "49") (pinfunction "(T1)PD6_49") (pintype "bidirectional"))
    )
    (net (code "112") (name "unconnected-(IC3-(T3{slash}INT6)PE6-Pad8)") (class "Default")
      (node (ref "IC3") (pin "8") (pinfunction "(T3/INT6)PE6_8") (pintype "bidirectional"))
    )
    (net (code "113") (name "unconnected-(IC3-(TOSC1)PG4-Pad29)") (class "Default")
      (node (ref "IC3") (pin "29") (pinfunction "(TOSC1)PG4_29") (pintype "bidirectional"))
    )
    (net (code "114") (name "unconnected-(IC3-(TOSC2)PG3-Pad28)") (class "Default")
      (node (ref "IC3") (pin "28") (pinfunction "(TOSC2)PG3_28") (pintype "bidirectional"))
    )
    (net (code "115") (name "unconnected-(IC3-(XCK0{slash}AIN0)PE2-Pad4)") (class "Default")
      (node (ref "IC3") (pin "4") (pinfunction "(XCK0/AIN0)PE2_4") (pintype "bidirectional"))
    )
    (net (code "116") (name "unconnected-(IC3-(XCK1)PD5-Pad48)") (class "Default")
      (node (ref "IC3") (pin "48") (pinfunction "(XCK1)PD5_48") (pintype "bidirectional"))
    )
    (net (code "117") (name "unconnected-(IC3-PH2(XCK2)-Pad14)") (class "Default")
      (node (ref "IC3") (pin "14") (pinfunction "PH2(XCK2)_14") (pintype "bidirectional"))
    )
    (net (code "118") (name "unconnected-(IC3-PH7(T4)-Pad27)") (class "Default")
      (node (ref "IC3") (pin "27") (pinfunction "PH7(T4)_27") (pintype "bidirectional"))
    )
    (net (code "119") (name "unconnected-(IC3-PJ2(XCK3{slash}PCINT11)-Pad65)") (class "Default")
      (node (ref "IC3") (pin "65") (pinfunction "PJ2(XCK3/PCINT11)_65") (pintype "bidirectional"))
    )
    (net (code "120") (name "unconnected-(IC3-PJ3(PCINT12)-Pad66)") (class "Default")
      (node (ref "IC3") (pin "66") (pinfunction "PJ3(PCINT12)_66") (pintype "bidirectional"))
    )
    (net (code "121") (name "unconnected-(IC3-PJ4(PCINT13)-Pad67)") (class "Default")
      (node (ref "IC3") (pin "67") (pinfunction "PJ4(PCINT13)_67") (pintype "bidirectional"))
    )
    (net (code "122") (name "unconnected-(IC3-PJ5(PCINT14)-Pad68)") (class "Default")
      (node (ref "IC3") (pin "68") (pinfunction "PJ5(PCINT14)_68") (pintype "bidirectional"))
    )
    (net (code "123") (name "unconnected-(IC3-PJ6(PCINT15)-Pad69)") (class "Default")
      (node (ref "IC3") (pin "69") (pinfunction "PJ6(PCINT15)_69") (pintype "bidirectional"))
    )
    (net (code "124") (name "unconnected-(IC3-PJ7-Pad79)") (class "Default")
      (node (ref "IC3") (pin "79") (pinfunction "PJ7_79") (pintype "bidirectional"))
    )
    (net (code "125") (name "unconnected-(IC4-(AIN0{slash}INT1)PD1-Pad7)") (class "Default")
      (node (ref "IC4") (pin "7") (pinfunction "(AIN0/INT1)PD1_7") (pintype "bidirectional"))
    )
    (net (code "126") (name "unconnected-(IC4-(AIN2{slash}PCINT11)PC2-Pad5)") (class "Default")
      (node (ref "IC4") (pin "5") (pinfunction "(AIN2/PCINT11)PC2_5") (pintype "bidirectional"))
    )
    (net (code "127") (name "unconnected-(IC4-(INT4{slash}ICP1{slash}CLK0)PC7-Pad22)") (class "Default")
      (node (ref "IC4") (pin "22") (pinfunction "(INT4/ICP1/CLK0)PC7_22") (pintype "bidirectional"))
    )
    (net (code "128") (name "unconnected-(IC4-(OC0B{slash}INT0)PD0-Pad6)") (class "Default")
      (node (ref "IC4") (pin "6") (pinfunction "(OC0B/INT0)PD0_6") (pintype "bidirectional"))
    )
    (net (code "129") (name "unconnected-(IC4-(OC1A{slash}PCINT8)PC6-Pad23)") (class "Default")
      (node (ref "IC4") (pin "23") (pinfunction "(OC1A/PCINT8)PC6_23") (pintype "bidirectional"))
    )
    (net (code "130") (name "unconnected-(IC4-(PCINT5)PB5-Pad19)") (class "Default")
      (node (ref "IC4") (pin "19") (pinfunction "(PCINT5)PB5_19") (pintype "bidirectional"))
    )
    (net (code "131") (name "unconnected-(IC4-(PCINT6)PB6-Pad20)") (class "Default")
      (node (ref "IC4") (pin "20") (pinfunction "(PCINT6)PB6_20") (pintype "bidirectional"))
    )
    (net (code "132") (name "unconnected-(IC4-(PCINT7{slash}OC0A{slash}OC1C)PB7-Pad21)") (class "Default")
      (node (ref "IC4") (pin "21") (pinfunction "(PCINT7/OC0A/OC1C)PB7_21") (pintype "bidirectional"))
    )
    (net (code "133") (name "unconnected-(IC4-(PCINT9{slash}OC1B)PC5-Pad25)") (class "Default")
      (node (ref "IC4") (pin "25") (pinfunction "(PCINT9/OC1B)PC5_25") (pintype "bidirectional"))
    )
    (net (code "134") (name "unconnected-(IC4-(PCINT10)PC4-Pad26)") (class "Default")
      (node (ref "IC4") (pin "26") (pinfunction "(PCINT10)PC4_26") (pintype "bidirectional"))
    )
    (net (code "135") (name "unconnected-(IC4-(RTS{slash}AIN5{slash}INT6)PD6-Pad12)") (class "Default")
      (node (ref "IC4") (pin "12") (pinfunction "(RTS/AIN5/INT6)PD6_12") (pintype "bidirectional"))
    )
    (net (code "136") (name "unconnected-(IC4-(SS{slash}PCINT0)PB0-Pad14)") (class "Default")
      (node (ref "IC4") (pin "14") (pinfunction "(SS/PCINT0)PB0_14") (pintype "bidirectional"))
    )
    (net (code "137") (name "unconnected-(IC4-(T1{slash}PCINT4)PB4-Pad18)") (class "Default")
      (node (ref "IC4") (pin "18") (pinfunction "(T1/PCINT4)PB4_18") (pintype "bidirectional"))
    )
    (net (code "138") (name "unconnected-(IC5A-OUT-Pad1)") (class "Default")
      (node (ref "IC5") (pin "1") (pinfunction "OUT_1") (pintype "output"))
    )
    (net (code "139") (name "unconnected-(IC6-NC{slash}FB-Pad4)") (class "Default")
      (node (ref "IC6") (pin "4") (pinfunction "NC/FB_4") (pintype "passive"))
    )
    (net (code "140") (name "unconnected-(RN1D-1-Pad4)") (class "Default")
      (node (ref "RN1") (pin "4") (pinfunction "1_4") (pintype "passive"))
    )
    (net (code "141") (name "unconnected-(RN1D-2-Pad5)") (class "Default")
      (node (ref "RN1") (pin "5") (pinfunction "2_5") (pintype "passive"))
    )
    (net (code "142") (name "unconnected-(RN2B-1-Pad2)") (class "Default")
      (node (ref "RN2") (pin "2") (pinfunction "1_2") (pintype "passive"))
    )
    (net (code "143") (name "unconnected-(RN2B-2-Pad7)") (class "Default")
      (node (ref "RN2") (pin "7") (pinfunction "2_7") (pintype "passive"))
    )
    (net (code "144") (name "unconnected-(RN2C-1-Pad3)") (class "Default")
      (node (ref "RN2") (pin "3") (pinfunction "1_3") (pintype "passive"))
    )
    (net (code "145") (name "unconnected-(RN2C-2-Pad6)") (class "Default")
      (node (ref "RN2") (pin "6") (pinfunction "2_6") (pintype "passive"))
    )
    (net (code "146") (name "unconnected-(RN3-Pad1)") (class "Default")
      (node (ref "RN3") (pin "1") (pinfunction "1_1") (pintype "passive"))
    )
    (net (code "147") (name "unconnected-(RN3A-2-Pad8)") (class "Default")
      (node (ref "RN3") (pin "8") (pinfunction "2_8") (pintype "passive"))
    )
    (net (code "148") (name "unconnected-(RN3B-1-Pad2)") (class "Default")
      (node (ref "RN3") (pin "2") (pinfunction "1_2") (pintype "passive"))
    )
    (net (code "149") (name "unconnected-(RN3B-2-Pad7)") (class "Default")
      (node (ref "RN3") (pin "7") (pinfunction "2_7") (pintype "passive"))
    )
    (net (code "150") (name "unconnected-(RN5D-1-Pad4)") (class "Default")
      (node (ref "RN5") (pin "4") (pinfunction "1_4") (pintype "passive"))
    )
    (net (code "151") (name "unconnected-(RN5D-2-Pad5)") (class "Default")
      (node (ref "RN5") (pin "5") (pinfunction "2_5") (pintype "passive"))
    )
  )
)
